# ui-jetson-nano.net
KiCad netlist of a schematic drawn in Altium Designer
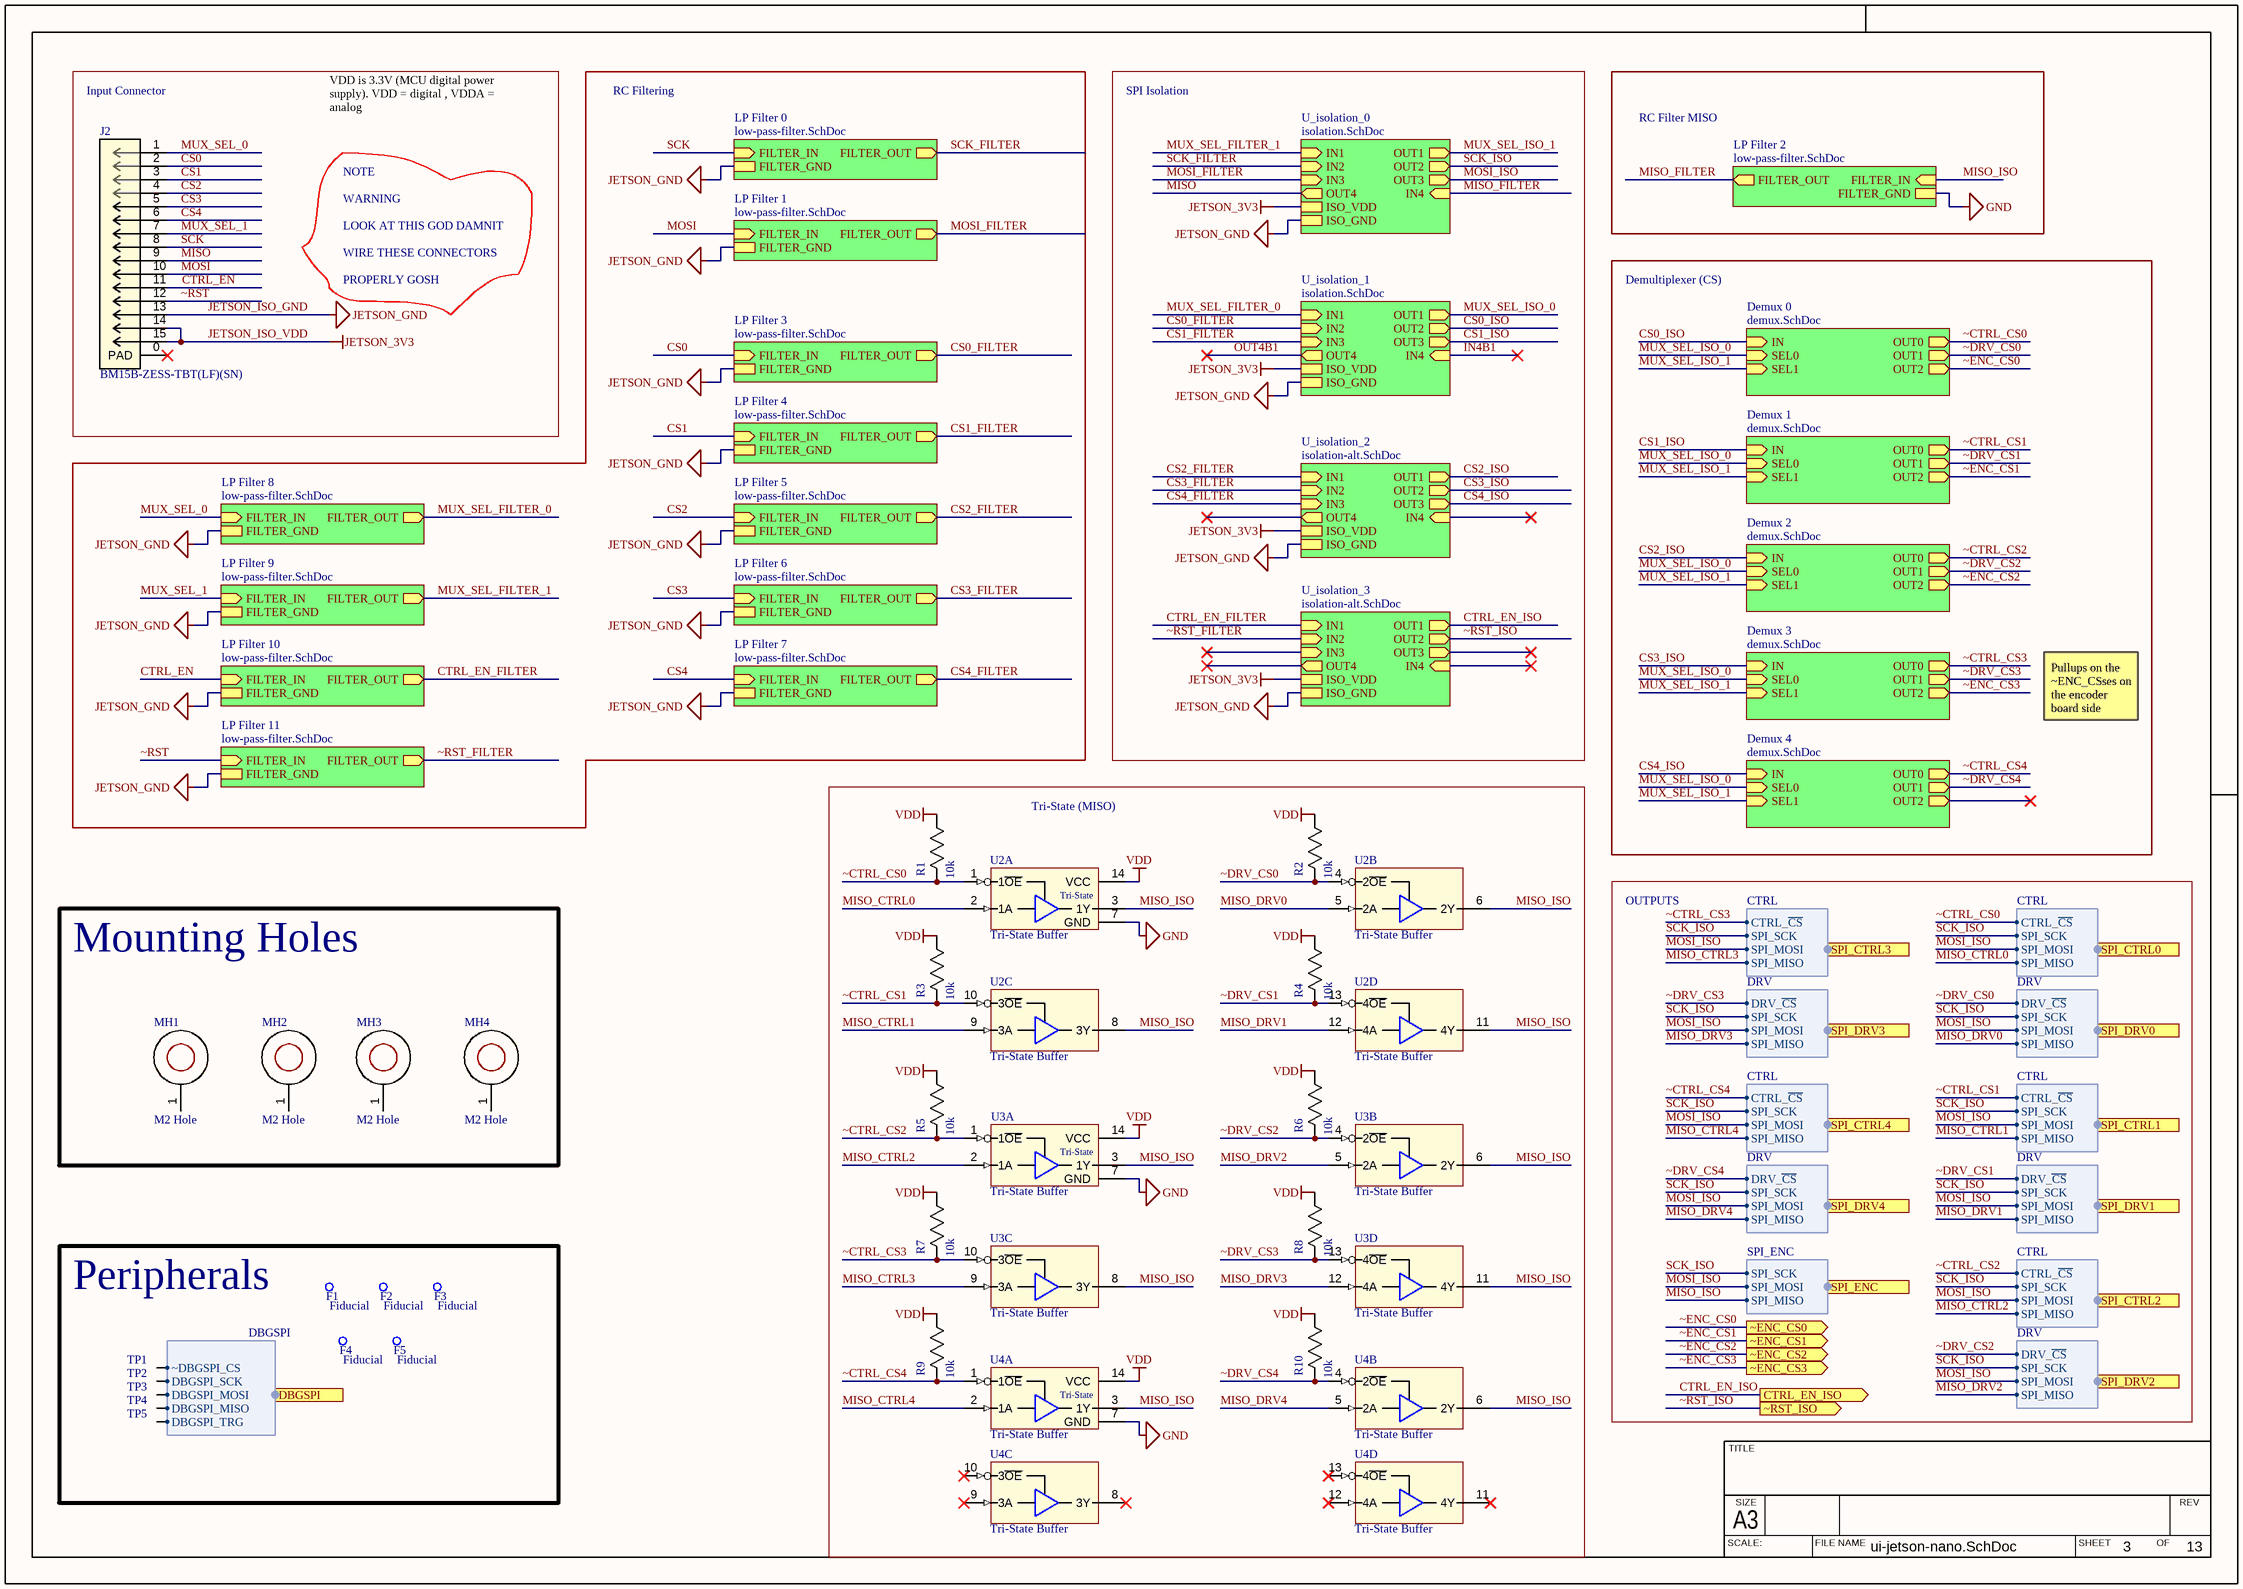
[diagram p0: ui-jetson-nano.SchDoc]

(export (version "E")
  (design (tool "Eeschema 10.0.6"))
  (components
    (comp (ref "F1")
      (value "Fiducial")
      (footprint "Fiducial")
      (libsource (lib "IC_Library") (part "Fiducial"))
    )
    (comp (ref "F2")
      (value "Fiducial")
      (footprint "Fiducial")
      (libsource (lib "IC_Library") (part "Fiducial"))
    )
    (comp (ref "F3")
      (value "Fiducial")
      (footprint "Fiducial")
      (libsource (lib "IC_Library") (part "Fiducial"))
    )
    (comp (ref "F4")
      (value "Fiducial")
      (footprint "Fiducial")
      (libsource (lib "IC_Library") (part "Fiducial"))
    )
    (comp (ref "F5")
      (value "Fiducial")
      (footprint "Fiducial")
      (libsource (lib "IC_Library") (part "Fiducial"))
    )
    (comp (ref "J2")
      (value "BM15B-ZESS-TBT(LF)(SN)")
      (footprint "JST ZE SMT 15POS")
      (description "CONN HEADER VERT SMD 15POS ZE")
      (fields (field (name "PART NUMBER") "CN 15POS JST ZE SMT"))
      (libsource (lib "Connector_Library") (part "CN 15POS JST ZE SMT"))
    )
    (comp (ref "MH1")
      (value "M2 Hole")
      (footprint "Mounting Hole M2")
      (description "Standard M2 Mounting Hole for M2 Standoff")
      (fields (field (name "PART NUMBER") "MOUNTING HOLE M2"))
      (libsource (lib "IC_Library") (part "MOUNTING HOLE M2"))
    )
    (comp (ref "MH2")
      (value "M2 Hole")
      (footprint "Mounting Hole M2")
      (description "Standard M2 Mounting Hole for M2 Standoff")
      (fields (field (name "PART NUMBER") "MOUNTING HOLE M2"))
      (libsource (lib "IC_Library") (part "MOUNTING HOLE M2"))
    )
    (comp (ref "MH3")
      (value "M2 Hole")
      (footprint "Mounting Hole M2")
      (description "Standard M2 Mounting Hole for M2 Standoff")
      (fields (field (name "PART NUMBER") "MOUNTING HOLE M2"))
      (libsource (lib "IC_Library") (part "MOUNTING HOLE M2"))
    )
    (comp (ref "MH4")
      (value "M2 Hole")
      (footprint "Mounting Hole M2")
      (description "Standard M2 Mounting Hole for M2 Standoff")
      (fields (field (name "PART NUMBER") "MOUNTING HOLE M2"))
      (libsource (lib "IC_Library") (part "MOUNTING HOLE M2"))
    )
    (comp (ref "R1")
      (value "10k")
      (footprint "0603")
      (description "RES SMD 10K OHM 1% 1/8W 0805")
      (fields (field (name "TOLERANCE") "5%") (field (name "PART NUMBER") "RES 10k 1/8W 1%"))
      (libsource (lib "Resistor_Library") (part "RES_DEFAULT"))
    )
    (comp (ref "R2")
      (value "10k")
      (footprint "0603")
      (description "RES SMD 10K OHM 1% 1/8W 0805")
      (fields (field (name "TOLERANCE") "5%") (field (name "PART NUMBER") "RES 10k 1/8W 1%"))
      (libsource (lib "Resistor_Library") (part "RES_DEFAULT"))
    )
    (comp (ref "R3")
      (value "10k")
      (footprint "0603")
      (description "RES SMD 10K OHM 1% 1/8W 0805")
      (fields (field (name "TOLERANCE") "5%") (field (name "PART NUMBER") "RES 10k 1/8W 1%"))
      (libsource (lib "Resistor_Library") (part "RES_DEFAULT"))
    )
    (comp (ref "R4")
      (value "10k")
      (footprint "0603")
      (description "RES SMD 10K OHM 1% 1/8W 0805")
      (fields (field (name "TOLERANCE") "5%") (field (name "PART NUMBER") "RES 10k 1/8W 1%"))
      (libsource (lib "Resistor_Library") (part "RES_DEFAULT"))
    )
    (comp (ref "R5")
      (value "10k")
      (footprint "0603")
      (description "RES SMD 10K OHM 1% 1/8W 0805")
      (fields (field (name "TOLERANCE") "5%") (field (name "PART NUMBER") "RES 10k 1/8W 1%"))
      (libsource (lib "Resistor_Library") (part "RES_DEFAULT"))
    )
    (comp (ref "R6")
      (value "10k")
      (footprint "0603")
      (description "RES SMD 10K OHM 1% 1/8W 0805")
      (fields (field (name "TOLERANCE") "5%") (field (name "PART NUMBER") "RES 10k 1/8W 1%"))
      (libsource (lib "Resistor_Library") (part "RES_DEFAULT"))
    )
    (comp (ref "R7")
      (value "10k")
      (footprint "0603")
      (description "RES SMD 10K OHM 1% 1/8W 0805")
      (fields (field (name "TOLERANCE") "5%") (field (name "PART NUMBER") "RES 10k 1/8W 1%"))
      (libsource (lib "Resistor_Library") (part "RES_DEFAULT"))
    )
    (comp (ref "R8")
      (value "10k")
      (footprint "0603")
      (description "RES SMD 10K OHM 1% 1/8W 0805")
      (fields (field (name "TOLERANCE") "5%") (field (name "PART NUMBER") "RES 10k 1/8W 1%"))
      (libsource (lib "Resistor_Library") (part "RES_DEFAULT"))
    )
    (comp (ref "R9")
      (value "10k")
      (footprint "0603")
      (description "RES SMD 10K OHM 1% 1/8W 0805")
      (fields (field (name "TOLERANCE") "5%") (field (name "PART NUMBER") "RES 10k 1/8W 1%"))
      (libsource (lib "Resistor_Library") (part "RES_DEFAULT"))
    )
    (comp (ref "R10")
      (value "10k")
      (footprint "0603")
      (description "RES SMD 10K OHM 1% 1/8W 0805")
      (fields (field (name "TOLERANCE") "5%") (field (name "PART NUMBER") "RES 10k 1/8W 1%"))
      (libsource (lib "Resistor_Library") (part "RES_DEFAULT"))
    )
    (comp (ref "TP1")
      (value "DBG_CS")
      (footprint "TP")
      (fields (field (name "PART NUMBER") "Test Point (Via)"))
      (libsource (lib "IC_Library") (part "Test Point (Via)"))
    )
    (comp (ref "TP2")
      (value "DBG_SCK")
      (footprint "TP")
      (fields (field (name "PART NUMBER") "Test Point (Via)"))
      (libsource (lib "IC_Library") (part "Test Point (Via)"))
    )
    (comp (ref "TP3")
      (value "DBG_MOSI")
      (footprint "TP")
      (fields (field (name "PART NUMBER") "Test Point (Via)"))
      (libsource (lib "IC_Library") (part "Test Point (Via)"))
    )
    (comp (ref "TP4")
      (value "DBG_MISO")
      (footprint "TP")
      (fields (field (name "PART NUMBER") "Test Point (Via)"))
      (libsource (lib "IC_Library") (part "Test Point (Via)"))
    )
    (comp (ref "TP5")
      (value "DBG_TRG")
      (footprint "TP")
      (fields (field (name "PART NUMBER") "Test Point (Via)"))
      (libsource (lib "IC_Library") (part "Test Point (Via)"))
    )
    (comp (ref "U2")
      (value "Tri-State Buffer")
      (footprint "14-TSSOP")
      (description "Buffer, Non-Inverting 4 Element 1 Bit per Element 3-State Output 14-TSSOP")
      (fields (field (name "PART NUMBER") "SN74LVC125APWR"))
      (libsource (lib "IC_Library") (part "SN74LVC125APWR"))
    )
    (comp (ref "U3")
      (value "Tri-State Buffer")
      (footprint "14-TSSOP")
      (description "Buffer, Non-Inverting 4 Element 1 Bit per Element 3-State Output 14-TSSOP")
      (fields (field (name "PART NUMBER") "SN74LVC125APWR"))
      (libsource (lib "IC_Library") (part "SN74LVC125APWR"))
    )
    (comp (ref "U4")
      (value "Tri-State Buffer")
      (footprint "14-TSSOP")
      (description "Buffer, Non-Inverting 4 Element 1 Bit per Element 3-State Output 14-TSSOP")
      (fields (field (name "PART NUMBER") "SN74LVC125APWR"))
      (libsource (lib "IC_Library") (part "SN74LVC125APWR"))
    )
  )
  (nets
    (net (code "5") (name "/CS0") (class "Default")
      (node (ref "J2") (pin "2") (pinfunction "2_2") (pintype "passive"))
    )
    (net (code "8") (name "/CS1") (class "Default")
      (node (ref "J2") (pin "3") (pinfunction "3_3") (pintype "passive"))
    )
    (net (code "11") (name "/CS2") (class "Default")
      (node (ref "J2") (pin "4") (pinfunction "4_4") (pintype "passive"))
    )
    (net (code "14") (name "/CS3") (class "Default")
      (node (ref "J2") (pin "5") (pinfunction "5_5") (pintype "passive"))
    )
    (net (code "17") (name "/CS4") (class "Default")
      (node (ref "J2") (pin "6") (pinfunction "6_6") (pintype "passive"))
    )
    (net (code "20") (name "/CTRL_EN") (class "Default")
      (node (ref "J2") (pin "11") (pinfunction "11_11") (pintype "passive"))
    )
    (net (code "23") (name "/DBGSPI_MISO") (class "Default")
      (node (ref "TP4") (pin "1") (pinfunction "1_1") (pintype "passive"))
    )
    (net (code "24") (name "/DBGSPI_MOSI") (class "Default")
      (node (ref "TP3") (pin "1") (pinfunction "1_1") (pintype "passive"))
    )
    (net (code "25") (name "/DBGSPI_SCK") (class "Default")
      (node (ref "TP2") (pin "1") (pinfunction "1_1") (pintype "passive"))
    )
    (net (code "26") (name "/DBGSPI_TRG") (class "Default")
      (node (ref "TP5") (pin "1") (pinfunction "1_1") (pintype "passive"))
    )
    (net (code "31") (name "/MISO") (class "Default")
      (node (ref "J2") (pin "9") (pinfunction "9_9") (pintype "passive"))
    )
    (net (code "32") (name "/MISO_CTRL0") (class "Default")
      (node (ref "U2") (pin "2") (pinfunction "1A_2") (pintype "input"))
    )
    (net (code "33") (name "/MISO_CTRL1") (class "Default")
      (node (ref "U2") (pin "9") (pinfunction "3A_9") (pintype "input"))
    )
    (net (code "34") (name "/MISO_CTRL2") (class "Default")
      (node (ref "U3") (pin "2") (pinfunction "1A_2") (pintype "input"))
    )
    (net (code "35") (name "/MISO_CTRL3") (class "Default")
      (node (ref "U3") (pin "9") (pinfunction "3A_9") (pintype "input"))
    )
    (net (code "36") (name "/MISO_CTRL4") (class "Default")
      (node (ref "U4") (pin "2") (pinfunction "1A_2") (pintype "input"))
    )
    (net (code "37") (name "/MISO_DRV0") (class "Default")
      (node (ref "U2") (pin "5") (pinfunction "2A_5") (pintype "input"))
    )
    (net (code "38") (name "/MISO_DRV1") (class "Default")
      (node (ref "U2") (pin "12") (pinfunction "4A_12") (pintype "input"))
    )
    (net (code "39") (name "/MISO_DRV2") (class "Default")
      (node (ref "U3") (pin "5") (pinfunction "2A_5") (pintype "input"))
    )
    (net (code "40") (name "/MISO_DRV3") (class "Default")
      (node (ref "U3") (pin "12") (pinfunction "4A_12") (pintype "input"))
    )
    (net (code "41") (name "/MISO_DRV4") (class "Default")
      (node (ref "U4") (pin "5") (pinfunction "2A_5") (pintype "input"))
    )
    (net (code "43") (name "/MISO_ISO") (class "Default")
      (node (ref "U2") (pin "11") (pinfunction "4Y_11") (pintype "passive"))
      (node (ref "U2") (pin "3") (pinfunction "1Y_3") (pintype "passive"))
      (node (ref "U2") (pin "6") (pinfunction "2Y_6") (pintype "passive"))
      (node (ref "U2") (pin "8") (pinfunction "3Y_8") (pintype "passive"))
      (node (ref "U3") (pin "11") (pinfunction "4Y_11") (pintype "passive"))
      (node (ref "U3") (pin "3") (pinfunction "1Y_3") (pintype "passive"))
      (node (ref "U3") (pin "6") (pinfunction "2Y_6") (pintype "passive"))
      (node (ref "U3") (pin "8") (pinfunction "3Y_8") (pintype "passive"))
      (node (ref "U4") (pin "3") (pinfunction "1Y_3") (pintype "passive"))
      (node (ref "U4") (pin "6") (pinfunction "2Y_6") (pintype "passive"))
    )
    (net (code "44") (name "/MOSI") (class "Default")
      (node (ref "J2") (pin "10") (pinfunction "10_10") (pintype "passive"))
    )
    (net (code "47") (name "/MUX_SEL_0") (class "Default")
      (node (ref "J2") (pin "1") (pinfunction "1_1") (pintype "passive"))
    )
    (net (code "48") (name "/MUX_SEL_1") (class "Default")
      (node (ref "J2") (pin "7") (pinfunction "7_7") (pintype "passive"))
    )
    (net (code "58") (name "/SCK") (class "Default")
      (node (ref "J2") (pin "8") (pinfunction "8_8") (pintype "passive"))
    )
    (net (code "65") (name "/~CTRL_CS0") (class "Default")
      (node (ref "R1") (pin "2") (pinfunction "R2_2") (pintype "passive"))
      (node (ref "U2") (pin "1") (pinfunction "1~{OE}_1") (pintype "input"))
    )
    (net (code "66") (name "/~CTRL_CS1") (class "Default")
      (node (ref "R3") (pin "2") (pinfunction "R2_2") (pintype "passive"))
      (node (ref "U2") (pin "10") (pinfunction "3~{OE}_10") (pintype "input"))
    )
    (net (code "67") (name "/~CTRL_CS2") (class "Default")
      (node (ref "R5") (pin "2") (pinfunction "R2_2") (pintype "passive"))
      (node (ref "U3") (pin "1") (pinfunction "1~{OE}_1") (pintype "input"))
    )
    (net (code "68") (name "/~CTRL_CS3") (class "Default")
      (node (ref "R7") (pin "2") (pinfunction "R2_2") (pintype "passive"))
      (node (ref "U3") (pin "10") (pinfunction "3~{OE}_10") (pintype "input"))
    )
    (net (code "69") (name "/~CTRL_CS4") (class "Default")
      (node (ref "R9") (pin "2") (pinfunction "R2_2") (pintype "passive"))
      (node (ref "U4") (pin "1") (pinfunction "1~{OE}_1") (pintype "input"))
    )
    (net (code "70") (name "/~DBGSPI_CS") (class "Default")
      (node (ref "TP1") (pin "1") (pinfunction "1_1") (pintype "passive"))
    )
    (net (code "71") (name "/~DRV_CS0") (class "Default")
      (node (ref "R2") (pin "2") (pinfunction "R2_2") (pintype "passive"))
      (node (ref "U2") (pin "4") (pinfunction "2~{OE}_4") (pintype "input"))
    )
    (net (code "72") (name "/~DRV_CS1") (class "Default")
      (node (ref "R4") (pin "2") (pinfunction "R2_2") (pintype "passive"))
      (node (ref "U2") (pin "13") (pinfunction "4~{OE}_13") (pintype "input"))
    )
    (net (code "73") (name "/~DRV_CS2") (class "Default")
      (node (ref "R6") (pin "2") (pinfunction "R2_2") (pintype "passive"))
      (node (ref "U3") (pin "4") (pinfunction "2~{OE}_4") (pintype "input"))
    )
    (net (code "74") (name "/~DRV_CS3") (class "Default")
      (node (ref "R8") (pin "2") (pinfunction "R2_2") (pintype "passive"))
      (node (ref "U3") (pin "13") (pinfunction "4~{OE}_13") (pintype "input"))
    )
    (net (code "75") (name "/~DRV_CS4") (class "Default")
      (node (ref "R10") (pin "2") (pinfunction "R2_2") (pintype "passive"))
      (node (ref "U4") (pin "4") (pinfunction "2~{OE}_4") (pintype "input"))
    )
    (net (code "80") (name "/~RST") (class "Default")
      (node (ref "J2") (pin "12") (pinfunction "12_12") (pintype "passive"))
    )
    (net (code "83") (name "GND") (class "Default")
      (node (ref "U2") (pin "7") (pinfunction "GND_7") (pintype "passive"))
      (node (ref "U3") (pin "7") (pinfunction "GND_7") (pintype "passive"))
      (node (ref "U4") (pin "7") (pinfunction "GND_7") (pintype "passive"))
    )
    (net (code "84") (name "JETSON_3V3") (class "Default")
      (node (ref "J2") (pin "14") (pinfunction "14_14") (pintype "passive"))
      (node (ref "J2") (pin "15") (pinfunction "15_15") (pintype "passive"))
    )
    (net (code "85") (name "JETSON_GND") (class "Default")
      (node (ref "J2") (pin "13") (pinfunction "13_13") (pintype "passive"))
    )
    (net (code "86") (name "VDD") (class "Default")
      (node (ref "R1") (pin "1") (pinfunction "R1_1") (pintype "passive"))
      (node (ref "R10") (pin "1") (pinfunction "R1_1") (pintype "passive"))
      (node (ref "R2") (pin "1") (pinfunction "R1_1") (pintype "passive"))
      (node (ref "R3") (pin "1") (pinfunction "R1_1") (pintype "passive"))
      (node (ref "R4") (pin "1") (pinfunction "R1_1") (pintype "passive"))
      (node (ref "R5") (pin "1") (pinfunction "R1_1") (pintype "passive"))
      (node (ref "R6") (pin "1") (pinfunction "R1_1") (pintype "passive"))
      (node (ref "R7") (pin "1") (pinfunction "R1_1") (pintype "passive"))
      (node (ref "R8") (pin "1") (pinfunction "R1_1") (pintype "passive"))
      (node (ref "R9") (pin "1") (pinfunction "R1_1") (pintype "passive"))
      (node (ref "U2") (pin "14") (pinfunction "VCC_14") (pintype "passive"))
      (node (ref "U3") (pin "14") (pinfunction "VCC_14") (pintype "passive"))
      (node (ref "U4") (pin "14") (pinfunction "VCC_14") (pintype "passive"))
    )
    (net (code "87") (name "unconnected-(J2-PAD-Pad0)") (class "Default")
      (node (ref "J2") (pin "0") (pinfunction "PAD_0") (pintype "passive+no_connect"))
    )
    (net (code "88") (name "unconnected-(MH1-Pad1)") (class "Default")
      (node (ref "MH1") (pin "1") (pinfunction "1_1") (pintype "passive"))
    )
    (net (code "89") (name "unconnected-(MH2-Pad1)") (class "Default")
      (node (ref "MH2") (pin "1") (pinfunction "1_1") (pintype "passive"))
    )
    (net (code "90") (name "unconnected-(MH3-Pad1)") (class "Default")
      (node (ref "MH3") (pin "1") (pinfunction "1_1") (pintype "passive"))
    )
    (net (code "91") (name "unconnected-(MH4-Pad1)") (class "Default")
      (node (ref "MH4") (pin "1") (pinfunction "1_1") (pintype "passive"))
    )
    (net (code "92") (name "unconnected-(U4C-3A-Pad9)") (class "Default")
      (node (ref "U4") (pin "9") (pinfunction "3A_9") (pintype "input+no_connect"))
    )
    (net (code "93") (name "unconnected-(U4C-3Y-Pad8)") (class "Default")
      (node (ref "U4") (pin "8") (pinfunction "3Y_8") (pintype "passive+no_connect"))
    )
    (net (code "94") (name "unconnected-(U4C-3~{OE}-Pad10)") (class "Default")
      (node (ref "U4") (pin "10") (pinfunction "3~{OE}_10") (pintype "input+no_connect"))
    )
    (net (code "95") (name "unconnected-(U4D-4A-Pad12)") (class "Default")
      (node (ref "U4") (pin "12") (pinfunction "4A_12") (pintype "input+no_connect"))
    )
    (net (code "96") (name "unconnected-(U4D-4Y-Pad11)") (class "Default")
      (node (ref "U4") (pin "11") (pinfunction "4Y_11") (pintype "passive+no_connect"))
    )
    (net (code "97") (name "unconnected-(U4D-4~{OE}-Pad13)") (class "Default")
      (node (ref "U4") (pin "13") (pinfunction "4~{OE}_13") (pintype "input+no_connect"))
    )
  )
)
